# 0084_-_Power.net
KiCad netlist of a schematic drawn in Altium Designer
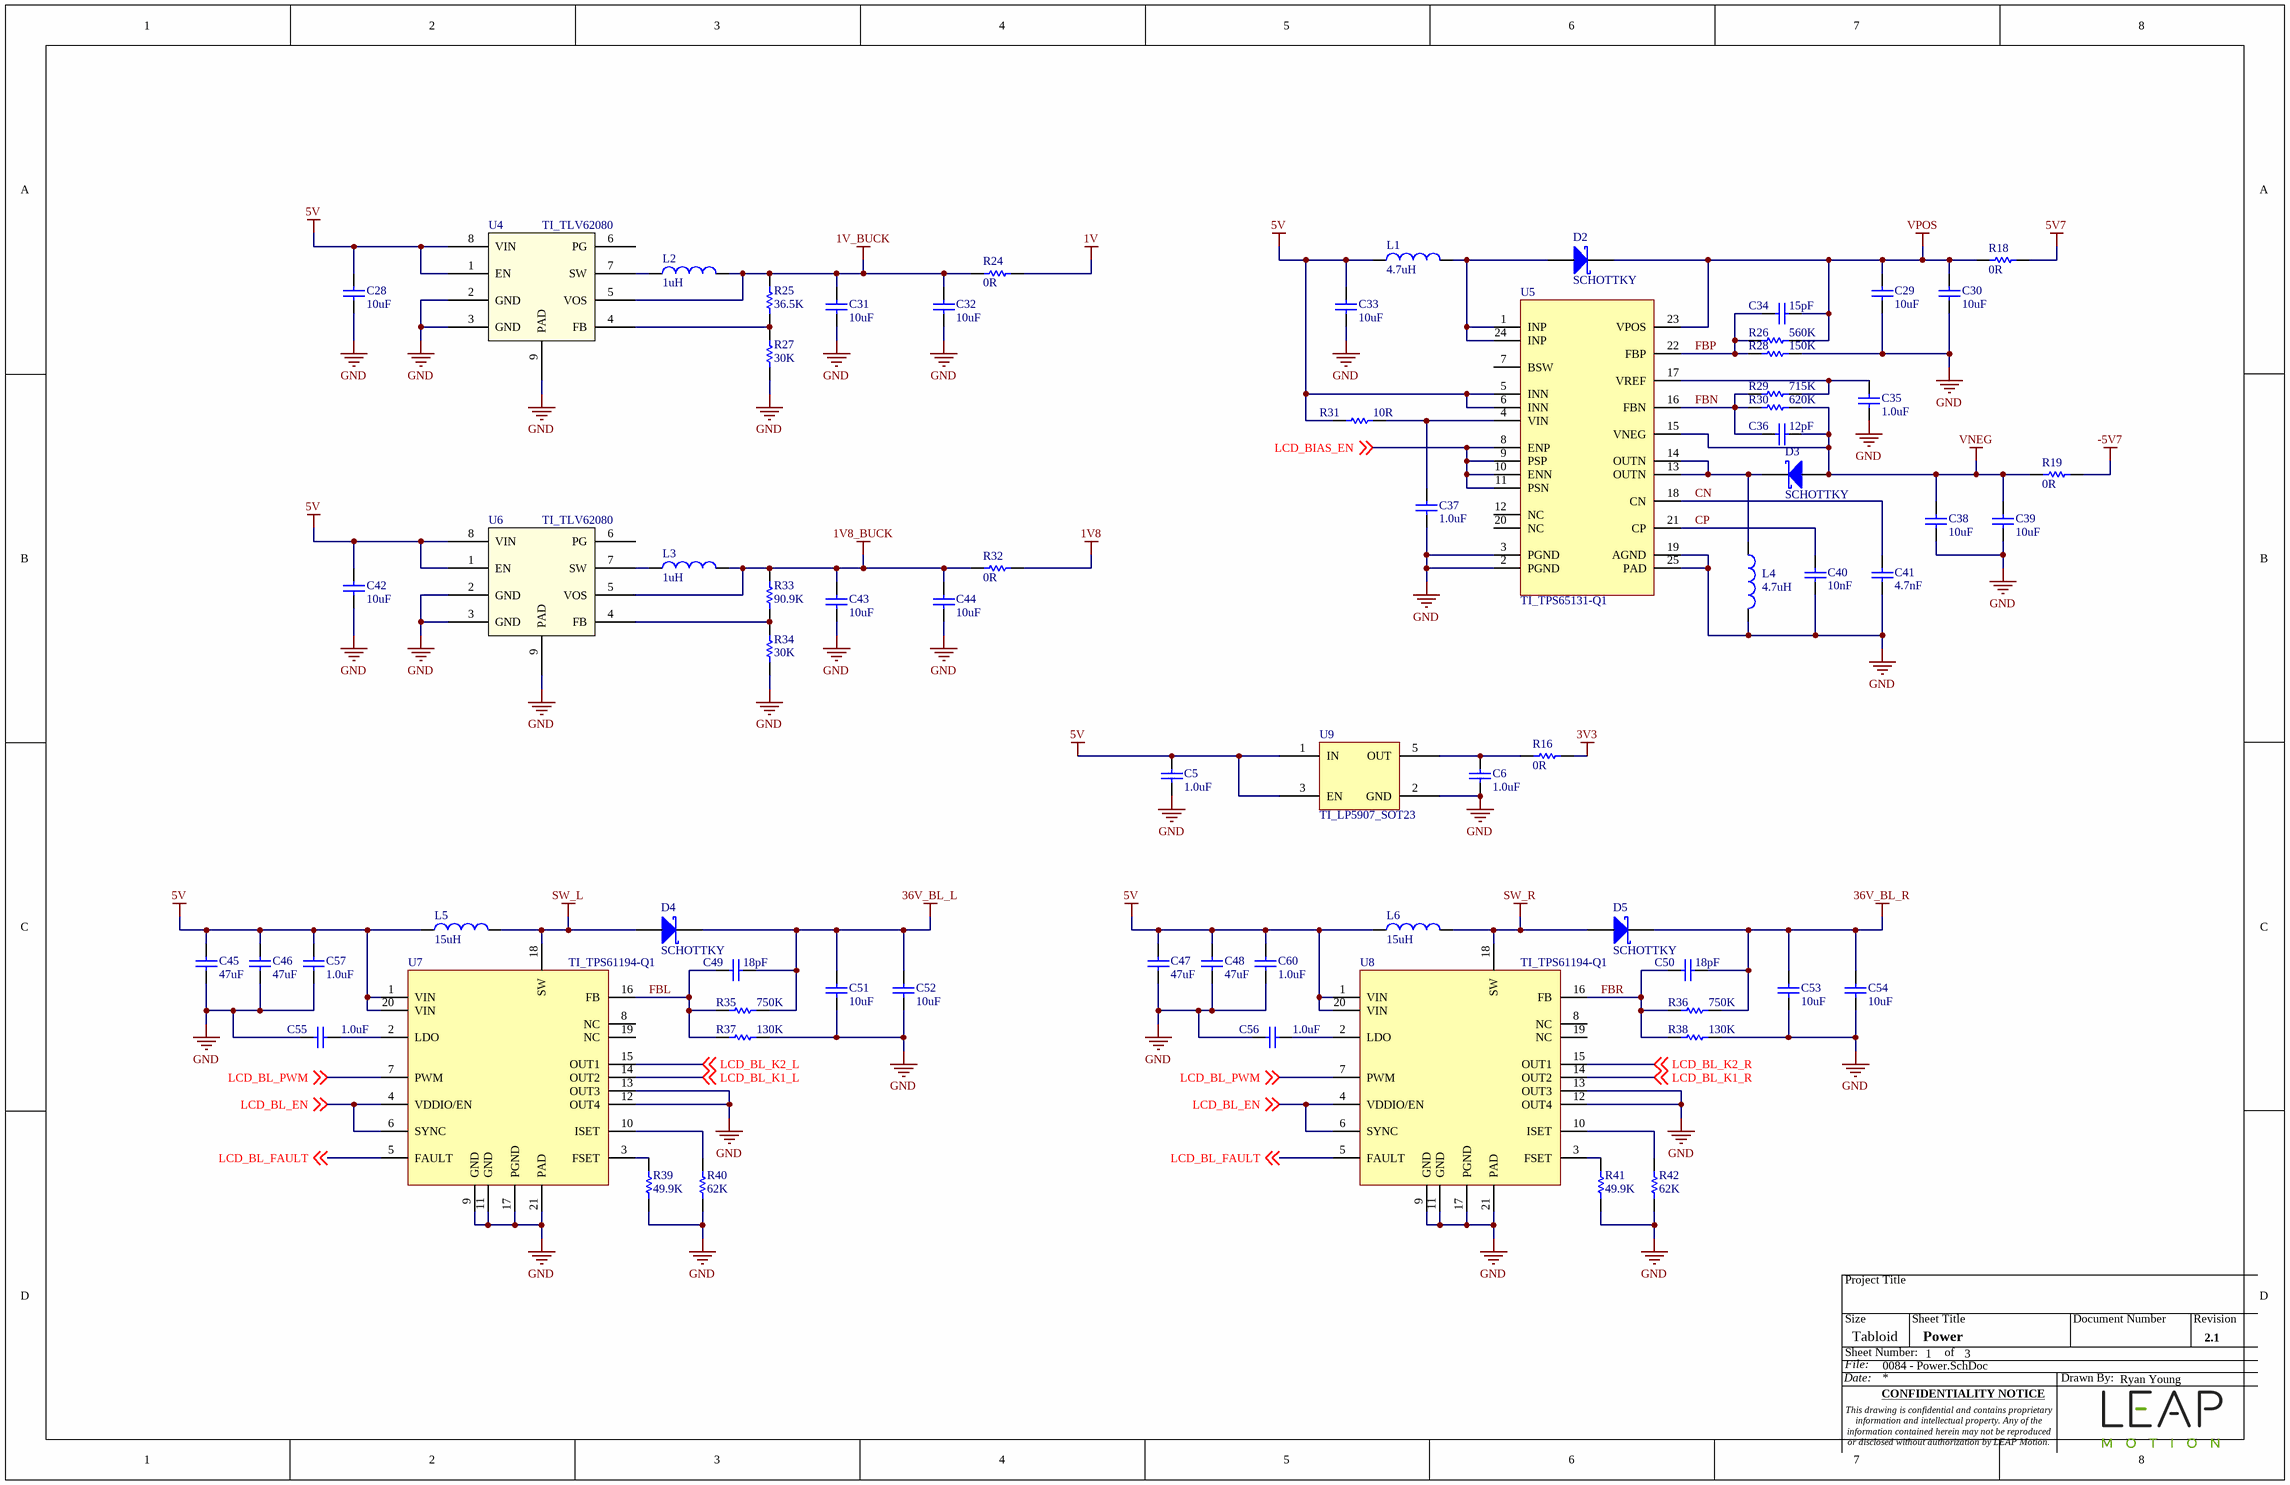
[diagram p0: 0084 - Power.SchDoc]

(export (version "E")
  (design (tool "Eeschema 10.0.6"))
  (components
    (comp (ref "C5")
      (value "1.0uF")
      (footprint "CAPC0402(1005)60_N")
      (description "Capacitor, 1.0uF, 10V, 10%, 0402, Ceramic, X5R")
      (fields
        (field (name "MANUFACTURER") "TDK")
        (field (name "TOLERANCE") "10%")
        (field (name "AUTHOR") "NR")
      )
      (libsource (lib "LEAPdb") (part "CAP"))
    )
    (comp (ref "C6")
      (value "1.0uF")
      (footprint "CAPC0402(1005)60_N")
      (description "Capacitor, 1.0uF, 10V, 10%, 0402, Ceramic, X5R")
      (fields
        (field (name "MANUFACTURER") "TDK")
        (field (name "TOLERANCE") "10%")
        (field (name "AUTHOR") "NR")
      )
      (libsource (lib "LEAPdb") (part "CAP"))
    )
    (comp (ref "C28")
      (value "10uF")
      (footprint "CAPC0603(1608)100_N")
      (description "Capacitor, 10uF, 10V, 10%, 0603, Ceramic, X5R")
      (fields
        (field (name "MANUFACTURER") "Murata")
        (field (name "TOLERANCE") "10%")
        (field (name "AUTHOR") "RY")
      )
      (libsource (lib "LEAPdb") (part "CAP"))
    )
    (comp (ref "C29")
      (value "10uF")
      (footprint "CAPC0603(1608)100_N")
      (description "Capacitor, 10uF, 10V, 10%, 0603, Ceramic, X5R")
      (fields
        (field (name "MANUFACTURER") "Murata")
        (field (name "TOLERANCE") "10%")
        (field (name "AUTHOR") "RY")
      )
      (libsource (lib "LEAPdb") (part "CAP"))
    )
    (comp (ref "C30")
      (value "10uF")
      (footprint "CAPC0603(1608)100_N")
      (description "Capacitor, 10uF, 10V, 10%, 0603, Ceramic, X5R")
      (fields
        (field (name "MANUFACTURER") "Murata")
        (field (name "TOLERANCE") "10%")
        (field (name "AUTHOR") "RY")
      )
      (libsource (lib "LEAPdb") (part "CAP"))
    )
    (comp (ref "C31")
      (value "10uF")
      (footprint "CAPC0603(1608)100_N")
      (description "Capacitor, 10uF, 10V, 10%, 0603, Ceramic, X5R")
      (fields
        (field (name "MANUFACTURER") "Murata")
        (field (name "TOLERANCE") "10%")
        (field (name "AUTHOR") "RY")
      )
      (libsource (lib "LEAPdb") (part "CAP"))
    )
    (comp (ref "C32")
      (value "10uF")
      (footprint "CAPC0603(1608)100_N")
      (description "Capacitor, 10uF, 10V, 10%, 0603, Ceramic, X5R")
      (fields
        (field (name "MANUFACTURER") "Murata")
        (field (name "TOLERANCE") "10%")
        (field (name "AUTHOR") "RY")
      )
      (libsource (lib "LEAPdb") (part "CAP"))
    )
    (comp (ref "C33")
      (value "10uF")
      (footprint "CAPC0603(1608)100_N")
      (description "Capacitor, 10uF, 10V, 10%, 0603, Ceramic, X5R")
      (fields
        (field (name "MANUFACTURER") "Murata")
        (field (name "TOLERANCE") "10%")
        (field (name "AUTHOR") "RY")
      )
      (libsource (lib "LEAPdb") (part "CAP"))
    )
    (comp (ref "C34")
      (value "15pF")
      (footprint "CAPC0201(0603)33_N")
      (description "Capacitor, 15pF, 50V, 2%, 0201, Ceramic, C0G(NP0)")
      (fields
        (field (name "MANUFACTURER") "Murata")
        (field (name "TOLERANCE") "2%")
        (field (name "AUTHOR") "RY")
      )
      (libsource (lib "LEAPdb") (part "CAP"))
    )
    (comp (ref "C35")
      (value "1.0uF")
      (footprint "CAPC0402(1005)60_N")
      (description "Capacitor, 1.0uF, 10V, 10%, 0402, Ceramic, X5R")
      (fields
        (field (name "MANUFACTURER") "TDK")
        (field (name "TOLERANCE") "10%")
        (field (name "AUTHOR") "NR")
      )
      (libsource (lib "LEAPdb") (part "CAP"))
    )
    (comp (ref "C36")
      (value "12pF")
      (footprint "CAPC0201(0603)33_N")
      (description "Capacitor, 12pF, 50V, 2%, 0201, Ceramic, C0G(NP0)")
      (fields
        (field (name "MANUFACTURER") "Murata")
        (field (name "TOLERANCE") "2%")
        (field (name "AUTHOR") "RY")
      )
      (libsource (lib "LEAPdb") (part "CAP"))
    )
    (comp (ref "C37")
      (value "1.0uF")
      (footprint "CAPC0402(1005)60_N")
      (description "Capacitor, 1.0uF, 10V, 10%, 0402, Ceramic, X5R")
      (fields
        (field (name "MANUFACTURER") "TDK")
        (field (name "TOLERANCE") "10%")
        (field (name "AUTHOR") "NR")
      )
      (libsource (lib "LEAPdb") (part "CAP"))
    )
    (comp (ref "C38")
      (value "10uF")
      (footprint "CAPC0603(1608)100_N")
      (description "Capacitor, 10uF, 10V, 10%, 0603, Ceramic, X5R")
      (fields
        (field (name "MANUFACTURER") "Murata")
        (field (name "TOLERANCE") "10%")
        (field (name "AUTHOR") "RY")
      )
      (libsource (lib "LEAPdb") (part "CAP"))
    )
    (comp (ref "C39")
      (value "10uF")
      (footprint "CAPC0603(1608)100_N")
      (description "Capacitor, 10uF, 10V, 10%, 0603, Ceramic, X5R")
      (fields
        (field (name "MANUFACTURER") "Murata")
        (field (name "TOLERANCE") "10%")
        (field (name "AUTHOR") "RY")
      )
      (libsource (lib "LEAPdb") (part "CAP"))
    )
    (comp (ref "C40")
      (value "10nF")
      (footprint "CAPC0402(1005)60_N")
      (description "Capacitor, 1.0uF, 10V, 10%, 0402, Ceramic, X5R")
      (fields
        (field (name "MANUFACTURER") "TDK")
        (field (name "TOLERANCE") "10%")
        (field (name "AUTHOR") "NR")
      )
      (libsource (lib "LEAPdb") (part "CAP"))
    )
    (comp (ref "C41")
      (value "4.7nF")
      (footprint "CAPC0402(1005)60_N")
      (description "Capacitor, 1.0uF, 10V, 10%, 0402, Ceramic, X5R")
      (fields
        (field (name "MANUFACTURER") "TDK")
        (field (name "TOLERANCE") "10%")
        (field (name "AUTHOR") "NR")
      )
      (libsource (lib "LEAPdb") (part "CAP"))
    )
    (comp (ref "C42")
      (value "10uF")
      (footprint "CAPC0603(1608)100_N")
      (description "Capacitor, 10uF, 10V, 10%, 0603, Ceramic, X5R")
      (fields
        (field (name "MANUFACTURER") "Murata")
        (field (name "TOLERANCE") "10%")
        (field (name "AUTHOR") "RY")
      )
      (libsource (lib "LEAPdb") (part "CAP"))
    )
    (comp (ref "C43")
      (value "10uF")
      (footprint "CAPC0603(1608)100_N")
      (description "Capacitor, 10uF, 10V, 10%, 0603, Ceramic, X5R")
      (fields
        (field (name "MANUFACTURER") "Murata")
        (field (name "TOLERANCE") "10%")
        (field (name "AUTHOR") "RY")
      )
      (libsource (lib "LEAPdb") (part "CAP"))
    )
    (comp (ref "C44")
      (value "10uF")
      (footprint "CAPC0603(1608)100_N")
      (description "Capacitor, 10uF, 10V, 10%, 0603, Ceramic, X5R")
      (fields
        (field (name "MANUFACTURER") "Murata")
        (field (name "TOLERANCE") "10%")
        (field (name "AUTHOR") "RY")
      )
      (libsource (lib "LEAPdb") (part "CAP"))
    )
    (comp (ref "C45")
      (value "47uF")
      (footprint "CAPC0805(2012)100_N")
      (description "Capacitor, 47uF, 10V, 20%, 0805, Ceramic, X5R")
      (fields
        (field (name "MANUFACTURER") "Murata")
        (field (name "TOLERANCE") "20%")
        (field (name "AUTHOR") "JDS")
      )
      (libsource (lib "LEAPdb") (part "CAP"))
    )
    (comp (ref "C46")
      (value "47uF")
      (footprint "CAPC0805(2012)100_N")
      (description "Capacitor, 47uF, 10V, 20%, 0805, Ceramic, X5R")
      (fields
        (field (name "MANUFACTURER") "Murata")
        (field (name "TOLERANCE") "20%")
        (field (name "AUTHOR") "JDS")
      )
      (libsource (lib "LEAPdb") (part "CAP"))
    )
    (comp (ref "C47")
      (value "47uF")
      (footprint "CAPC0805(2012)100_N")
      (description "Capacitor, 47uF, 10V, 20%, 0805, Ceramic, X5R")
      (fields
        (field (name "MANUFACTURER") "Murata")
        (field (name "TOLERANCE") "20%")
        (field (name "AUTHOR") "JDS")
      )
      (libsource (lib "LEAPdb") (part "CAP"))
    )
    (comp (ref "C48")
      (value "47uF")
      (footprint "CAPC0805(2012)100_N")
      (description "Capacitor, 47uF, 10V, 20%, 0805, Ceramic, X5R")
      (fields
        (field (name "MANUFACTURER") "Murata")
        (field (name "TOLERANCE") "20%")
        (field (name "AUTHOR") "JDS")
      )
      (libsource (lib "LEAPdb") (part "CAP"))
    )
    (comp (ref "C49")
      (value "18pF")
      (footprint "CAPC0201(0603)33_N")
      (description "Capacitor, 18pF, 50V, 2%, 0201, Ceramic, C0G(NP0)")
      (fields
        (field (name "MANUFACTURER") "Murata")
        (field (name "TOLERANCE") "2%")
        (field (name "AUTHOR") "RY")
      )
      (libsource (lib "LEAPdb") (part "CAP"))
    )
    (comp (ref "C50")
      (value "18pF")
      (footprint "CAPC0201(0603)33_N")
      (description "Capacitor, 18pF, 50V, 2%, 0201, Ceramic, C0G(NP0)")
      (fields
        (field (name "MANUFACTURER") "Murata")
        (field (name "TOLERANCE") "2%")
        (field (name "AUTHOR") "RY")
      )
      (libsource (lib "LEAPdb") (part "CAP"))
    )
    (comp (ref "C51")
      (value "10uF")
      (footprint "CAPC1206(3216)170_N")
      (description "Capacitor, 10uF, 50V, 10%, 1206, Ceramic, X7R")
      (fields
        (field (name "MANUFACTURER") "Samsung")
        (field (name "TOLERANCE") "10%")
        (field (name "AUTHOR") "RY")
      )
      (libsource (lib "LEAPdb") (part "CAP"))
    )
    (comp (ref "C52")
      (value "10uF")
      (footprint "CAPC1206(3216)170_N")
      (description "Capacitor, 10uF, 50V, 10%, 1206, Ceramic, X7R")
      (fields
        (field (name "MANUFACTURER") "Samsung")
        (field (name "TOLERANCE") "10%")
        (field (name "AUTHOR") "RY")
      )
      (libsource (lib "LEAPdb") (part "CAP"))
    )
    (comp (ref "C53")
      (value "10uF")
      (footprint "CAPC1206(3216)170_N")
      (description "Capacitor, 10uF, 50V, 10%, 1206, Ceramic, X7R")
      (fields
        (field (name "MANUFACTURER") "Samsung")
        (field (name "TOLERANCE") "10%")
        (field (name "AUTHOR") "RY")
      )
      (libsource (lib "LEAPdb") (part "CAP"))
    )
    (comp (ref "C54")
      (value "10uF")
      (footprint "CAPC1206(3216)170_N")
      (description "Capacitor, 10uF, 50V, 10%, 1206, Ceramic, X7R")
      (fields
        (field (name "MANUFACTURER") "Samsung")
        (field (name "TOLERANCE") "10%")
        (field (name "AUTHOR") "RY")
      )
      (libsource (lib "LEAPdb") (part "CAP"))
    )
    (comp (ref "C55")
      (value "1.0uF")
      (footprint "CAPC0402(1005)60_N")
      (description "Capacitor, 1.0uF, 10V, 10%, 0402, Ceramic, X5R")
      (fields
        (field (name "MANUFACTURER") "TDK")
        (field (name "TOLERANCE") "10%")
        (field (name "AUTHOR") "NR")
      )
      (libsource (lib "LEAPdb") (part "CAP"))
    )
    (comp (ref "C56")
      (value "1.0uF")
      (footprint "CAPC0402(1005)60_N")
      (description "Capacitor, 1.0uF, 10V, 10%, 0402, Ceramic, X5R")
      (fields
        (field (name "MANUFACTURER") "TDK")
        (field (name "TOLERANCE") "10%")
        (field (name "AUTHOR") "NR")
      )
      (libsource (lib "LEAPdb") (part "CAP"))
    )
    (comp (ref "C57")
      (value "1.0uF")
      (footprint "CAPC0402(1005)60_N")
      (description "Capacitor, 1.0uF, 10V, 10%, 0402, Ceramic, X5R")
      (fields
        (field (name "MANUFACTURER") "TDK")
        (field (name "TOLERANCE") "10%")
        (field (name "AUTHOR") "NR")
      )
      (libsource (lib "LEAPdb") (part "CAP"))
    )
    (comp (ref "C60")
      (value "1.0uF")
      (footprint "CAPC0402(1005)60_N")
      (description "Capacitor, 1.0uF, 10V, 10%, 0402, Ceramic, X5R")
      (fields
        (field (name "MANUFACTURER") "TDK")
        (field (name "TOLERANCE") "10%")
        (field (name "AUTHOR") "NR")
      )
      (libsource (lib "LEAPdb") (part "CAP"))
    )
    (comp (ref "D2")
      (value "SCHOTTKY")
      (footprint "Toshiba_CUS10S40,H3F")
      (description "Diode, -40C - 150C, SOD-323")
      (fields (field (name "MANUFACTURER") "Toshiba"))
      (libsource (lib "LEAPdb") (part "SCHOTTKY"))
    )
    (comp (ref "D3")
      (value "SCHOTTKY")
      (footprint "Toshiba_CUS10S40,H3F")
      (description "Diode, -40C - 150C, SOD-323")
      (fields (field (name "MANUFACTURER") "Toshiba"))
      (libsource (lib "LEAPdb") (part "SCHOTTKY"))
    )
    (comp (ref "D4")
      (value "SCHOTTKY")
      (footprint "Toshiba_CUS10S40,H3F")
      (description "Diode, -40C - 150C, SOD-323")
      (fields (field (name "MANUFACTURER") "Toshiba"))
      (libsource (lib "LEAPdb") (part "SCHOTTKY"))
    )
    (comp (ref "D5")
      (value "SCHOTTKY")
      (footprint "Toshiba_CUS10S40,H3F")
      (description "Diode, -40C - 150C, SOD-323")
      (fields (field (name "MANUFACTURER") "Toshiba"))
      (libsource (lib "LEAPdb") (part "SCHOTTKY"))
    )
    (comp (ref "L1")
      (value "4.7uH")
      (footprint "INDC2520X10N")
      (description "FIXED IND 4.7UH 1.4A 216 MOHM")
      (fields
        (field (name "MANUFACTURER") "Murata")
        (field (name "TOLERANCE") "20%")
        (field (name "AUTHOR") "RY")
      )
      (libsource (lib "LEAPdb") (part "Inductor"))
    )
    (comp (ref "L2")
      (value "1uH")
      (footprint "INDC2520X10N")
      (description "INDUCTOR 1.0UH 20% 1600MA 1008")
      (fields
        (field (name "MANUFACTURER") "Murata")
        (field (name "TOLERANCE") "20%")
        (field (name "AUTHOR") "NR")
      )
      (libsource (lib "LEAPdb") (part "Inductor"))
    )
    (comp (ref "L3")
      (value "1uH")
      (footprint "INDC2520X10N")
      (description "INDUCTOR 1.0UH 20% 1600MA 1008")
      (fields
        (field (name "MANUFACTURER") "Murata")
        (field (name "TOLERANCE") "20%")
        (field (name "AUTHOR") "NR")
      )
      (libsource (lib "LEAPdb") (part "Inductor"))
    )
    (comp (ref "L4")
      (value "4.7uH")
      (footprint "INDC2520X10N")
      (description "FIXED IND 4.7UH 1.4A 216 MOHM")
      (fields
        (field (name "MANUFACTURER") "Murata")
        (field (name "TOLERANCE") "20%")
        (field (name "AUTHOR") "RY")
      )
      (libsource (lib "LEAPdb") (part "Inductor"))
    )
    (comp (ref "L5")
      (value "15uH")
      (footprint "Coilcraft_XAL4040-153MEB")
      (description "Fixed Inductors XAL4040 AEC-Q200 15 uH 20 % 2.8 A")
      (fields
        (field (name "MANUFACTURER") "Coilcraft")
        (field (name "TOLERANCE") "20%")
        (field (name "AUTHOR") "RY")
      )
      (libsource (lib "LEAPdb") (part "Inductor"))
    )
    (comp (ref "L6")
      (value "15uH")
      (footprint "Coilcraft_XAL4040-153MEB")
      (description "Fixed Inductors XAL4040 AEC-Q200 15 uH 20 % 2.8 A")
      (fields
        (field (name "MANUFACTURER") "Coilcraft")
        (field (name "TOLERANCE") "20%")
        (field (name "AUTHOR") "RY")
      )
      (libsource (lib "LEAPdb") (part "Inductor"))
    )
    (comp (ref "R16")
      (value "0R")
      (footprint "RESC0402(1005)_N")
      (description "Resistor, 0R, 1/10W, Jumper, 0402")
      (fields
        (field (name "MANUFACTURER") "Panasonic Electronic Components")
        (field (name "TOLERANCE") "Jumper")
        (field (name "AUTHOR") "NR")
      )
      (libsource (lib "LEAPdb") (part "RES"))
    )
    (comp (ref "R18")
      (value "0R")
      (footprint "RESC0402(1005)_N")
      (description "Resistor, 0R, 1/10W, Jumper, 0402")
      (fields
        (field (name "MANUFACTURER") "Panasonic Electronic Components")
        (field (name "TOLERANCE") "Jumper")
        (field (name "AUTHOR") "NR")
      )
      (libsource (lib "LEAPdb") (part "RES"))
    )
    (comp (ref "R19")
      (value "0R")
      (footprint "RESC0402(1005)_N")
      (description "Resistor, 0R, 1/10W, Jumper, 0402")
      (fields
        (field (name "MANUFACTURER") "Panasonic Electronic Components")
        (field (name "TOLERANCE") "Jumper")
        (field (name "AUTHOR") "NR")
      )
      (libsource (lib "LEAPdb") (part "RES"))
    )
    (comp (ref "R24")
      (value "0R")
      (footprint "RESC0402(1005)_N")
      (description "Resistor, 0R, 1/10W, Jumper, 0402")
      (fields
        (field (name "MANUFACTURER") "Panasonic Electronic Components")
        (field (name "TOLERANCE") "Jumper")
        (field (name "AUTHOR") "NR")
      )
      (libsource (lib "LEAPdb") (part "RES"))
    )
    (comp (ref "R25")
      (value "36.5K")
      (footprint "RESC0201(0603)_N")
      (description "Resistor, 36.5K, 1/20W, 1%, 0201")
      (fields
        (field (name "MANUFACTURER") "Panasonic Electronic Components")
        (field (name "TOLERANCE") "1%")
        (field (name "AUTHOR") "RY")
      )
      (libsource (lib "LEAPdb") (part "RES"))
    )
    (comp (ref "R26")
      (value "560K")
      (footprint "RESC0201(0603)_N")
      (description "Resistor, 560K, 1/20W, 1%, 0201")
      (fields
        (field (name "MANUFACTURER") "Yageo")
        (field (name "TOLERANCE") "1%")
        (field (name "AUTHOR") "Ry")
      )
      (libsource (lib "LEAPdb") (part "RES"))
    )
    (comp (ref "R27")
      (value "30K")
      (footprint "RESC0201(0603)_N")
      (description "Resistor, 30K, 1/20W, 1%, 0201")
      (fields
        (field (name "MANUFACTURER") "Panasonic Electronic Components")
        (field (name "TOLERANCE") "1%")
        (field (name "AUTHOR") "RY")
      )
      (libsource (lib "LEAPdb") (part "RES"))
    )
    (comp (ref "R28")
      (value "150K")
      (footprint "RESC0201(0603)_N")
      (description "Resistor, 150K, 1/20W, 1%, 0201")
      (fields
        (field (name "MANUFACTURER") "Panasonic Electronic Components")
        (field (name "TOLERANCE") "1%")
        (field (name "AUTHOR") "RY")
      )
      (libsource (lib "LEAPdb") (part "RES"))
    )
    (comp (ref "R29")
      (value "715K")
      (footprint "RESC0201(0603)_N")
      (description "Resistor, 715K, 1/20W, 1%, 0201")
      (fields
        (field (name "MANUFACTURER") "Yageo")
        (field (name "TOLERANCE") "1%")
        (field (name "AUTHOR") "RY")
      )
      (libsource (lib "LEAPdb") (part "RES"))
    )
    (comp (ref "R30")
      (value "620K")
      (footprint "RESC0201(0603)_N")
      (description "Resistor, 620K, 1/20W, 1%, 0201")
      (fields
        (field (name "MANUFACTURER") "Panasonic Electronic Components")
        (field (name "TOLERANCE") "1%")
        (field (name "AUTHOR") "RY")
      )
      (libsource (lib "LEAPdb") (part "RES"))
    )
    (comp (ref "R31")
      (value "10R")
      (footprint "RESC0402(1005)_N")
      (description "Resistor, 10R, 1/10W, 1%, 0402")
      (fields
        (field (name "MANUFACTURER") "Panasonic")
        (field (name "TOLERANCE") "1%")
        (field (name "AUTHOR") "JDS")
      )
      (libsource (lib "LEAPdb") (part "RES"))
    )
    (comp (ref "R32")
      (value "0R")
      (footprint "RESC0402(1005)_N")
      (description "Resistor, 0R, 1/10W, Jumper, 0402")
      (fields
        (field (name "MANUFACTURER") "Panasonic Electronic Components")
        (field (name "TOLERANCE") "Jumper")
        (field (name "AUTHOR") "NR")
      )
      (libsource (lib "LEAPdb") (part "RES"))
    )
    (comp (ref "R33")
      (value "90.9K")
      (footprint "RESC0201(0603)_N")
      (description "Resistor, 90.9K, 1/20W, 1%, 0201")
      (fields
        (field (name "MANUFACTURER") "Panasonic Electronic Components")
        (field (name "TOLERANCE") "1%")
        (field (name "AUTHOR") "RY")
      )
      (libsource (lib "LEAPdb") (part "RES"))
    )
    (comp (ref "R34")
      (value "30K")
      (footprint "RESC0201(0603)_N")
      (description "Resistor, 30K, 1/20W, 1%, 0201")
      (fields
        (field (name "MANUFACTURER") "Panasonic Electronic Components")
        (field (name "TOLERANCE") "1%")
        (field (name "AUTHOR") "RY")
      )
      (libsource (lib "LEAPdb") (part "RES"))
    )
    (comp (ref "R35")
      (value "750K")
      (footprint "RESC0201(0603)_N")
      (description "Resistor, 750K, 1/20W, 1%, 0201")
      (fields
        (field (name "MANUFACTURER") "Panasonic Electronic Components")
        (field (name "TOLERANCE") "1%")
        (field (name "AUTHOR") "RY")
      )
      (libsource (lib "LEAPdb") (part "RES"))
    )
    (comp (ref "R36")
      (value "750K")
      (footprint "RESC0201(0603)_N")
      (description "Resistor, 750K, 1/20W, 1%, 0201")
      (fields
        (field (name "MANUFACTURER") "Panasonic Electronic Components")
        (field (name "TOLERANCE") "1%")
        (field (name "AUTHOR") "RY")
      )
      (libsource (lib "LEAPdb") (part "RES"))
    )
    (comp (ref "R37")
      (value "130K")
      (footprint "RESC0201(0603)_N")
      (description "Resistor, 130K, 1/20W, 1%, 0201")
      (fields
        (field (name "MANUFACTURER") "Panasonic Electronic Components")
        (field (name "TOLERANCE") "1%")
        (field (name "AUTHOR") "RY")
      )
      (libsource (lib "LEAPdb") (part "RES"))
    )
    (comp (ref "R38")
      (value "130K")
      (footprint "RESC0201(0603)_N")
      (description "Resistor, 130K, 1/20W, 1%, 0201")
      (fields
        (field (name "MANUFACTURER") "Panasonic Electronic Components")
        (field (name "TOLERANCE") "1%")
        (field (name "AUTHOR") "RY")
      )
      (libsource (lib "LEAPdb") (part "RES"))
    )
    (comp (ref "R39")
      (value "49.9K")
      (footprint "RESC0201(0603)_N")
      (description "Resistor, 49.9K, 1/20W, 1%, 0201")
      (fields
        (field (name "MANUFACTURER") "Panasonic Electronic Components")
        (field (name "TOLERANCE") "1%")
        (field (name "AUTHOR") "JDS")
      )
      (libsource (lib "LEAPdb") (part "RES"))
    )
    (comp (ref "R40")
      (value "62K")
      (footprint "RESC0201(0603)_N")
      (description "Resistor, 62K, 1/20W, 1%, 0201")
      (fields
        (field (name "MANUFACTURER") "Panasonic Electronic Components")
        (field (name "TOLERANCE") "1%")
        (field (name "AUTHOR") "NR")
      )
      (libsource (lib "LEAPdb") (part "RES"))
    )
    (comp (ref "R41")
      (value "49.9K")
      (footprint "RESC0201(0603)_N")
      (description "Resistor, 49.9K, 1/20W, 1%, 0201")
      (fields
        (field (name "MANUFACTURER") "Panasonic Electronic Components")
        (field (name "TOLERANCE") "1%")
        (field (name "AUTHOR") "JDS")
      )
      (libsource (lib "LEAPdb") (part "RES"))
    )
    (comp (ref "R42")
      (value "62K")
      (footprint "RESC0201(0603)_N")
      (description "Resistor, 62K, 1/20W, 1%, 0201")
      (fields
        (field (name "MANUFACTURER") "Panasonic Electronic Components")
        (field (name "TOLERANCE") "1%")
        (field (name "AUTHOR") "NR")
      )
      (libsource (lib "LEAPdb") (part "RES"))
    )
    (comp (ref "U4")
      (value "TI_TLV62080")
      (footprint "TI_TLV62080")
      (description "IC REG BUCK ADJ 1.2A SYNC 8WSON")
      (fields (field (name "MANUFACTURER") "TI") (field (name "AUTHOR") "RY"))
      (libsource (lib "LEAPdb") (part "TI_TLV62080"))
    )
    (comp (ref "U5")
      (value "TI_TPS65131-Q1")
      (footprint "TI_TPS65131-Q1")
      (description "IC REG BCK BST INV ADJ DL 24VQFN")
      (fields (field (name "MANUFACTURER") "TI") (field (name "AUTHOR") "RY"))
      (libsource (lib "LEAPdb") (part "TI_TPS65131-Q1"))
    )
    (comp (ref "U6")
      (value "TI_TLV62080")
      (footprint "TI_TLV62080")
      (description "IC REG BUCK ADJ 1.2A SYNC 8WSON")
      (fields (field (name "MANUFACTURER") "TI") (field (name "AUTHOR") "RY"))
      (libsource (lib "LEAPdb") (part "TI_TLV62080"))
    )
    (comp (ref "U7")
      (value "TI_TPS61194-Q1")
      (footprint "TI_TPS61194-Q1")
      (description "IC LED DRIVER 20TSSOP")
      (fields (field (name "MANUFACTURER") "TI") (field (name "AUTHOR") "RY"))
      (libsource (lib "LEAPdb") (part "TI_TPS61194-Q1"))
    )
    (comp (ref "U8")
      (value "TI_TPS61194-Q1")
      (footprint "TI_TPS61194-Q1")
      (description "IC LED DRIVER 20TSSOP")
      (fields (field (name "MANUFACTURER") "TI") (field (name "AUTHOR") "RY"))
      (libsource (lib "LEAPdb") (part "TI_TPS61194-Q1"))
    )
    (comp (ref "U9")
      (value "TI_LP5907_SOT23")
      (footprint "TI_LP5907_SOT23")
      (description "3.3 V LDO Voltage Regulators 250mA Ultra-Lo Noise LDO Reg")
      (fields (field (name "MANUFACTURER") "TI") (field (name "AUTHOR") "JDS"))
      (libsource (lib "LEAPdb") (part "TI_LP5907_SOT23"))
    )
  )
  (nets
    (net (code "1") (name "-5V7") (class "Default")
      (node (ref "R19") (pin "2") (pinfunction "2_2") (pintype "passive"))
    )
    (net (code "2") (name "/CN") (class "Default")
      (node (ref "C41") (pin "1") (pinfunction "1_1") (pintype "passive"))
      (node (ref "U5") (pin "18") (pinfunction "CN_18") (pintype "passive"))
    )
    (net (code "3") (name "/CP") (class "Default")
      (node (ref "C40") (pin "1") (pinfunction "1_1") (pintype "passive"))
      (node (ref "U5") (pin "21") (pinfunction "CP_21") (pintype "passive"))
    )
    (net (code "4") (name "/FBL") (class "Default")
      (node (ref "C49") (pin "2") (pinfunction "2_2") (pintype "passive"))
      (node (ref "R35") (pin "2") (pinfunction "2_2") (pintype "passive"))
      (node (ref "R37") (pin "2") (pinfunction "2_2") (pintype "passive"))
      (node (ref "U7") (pin "16") (pinfunction "FB_16") (pintype "passive"))
    )
    (net (code "5") (name "/FBN") (class "Default")
      (node (ref "C36") (pin "2") (pinfunction "2_2") (pintype "passive"))
      (node (ref "R29") (pin "2") (pinfunction "2_2") (pintype "passive"))
      (node (ref "R30") (pin "2") (pinfunction "2_2") (pintype "passive"))
      (node (ref "U5") (pin "16") (pinfunction "FBN_16") (pintype "passive"))
    )
    (net (code "6") (name "/FBP") (class "Default")
      (node (ref "C34") (pin "2") (pinfunction "2_2") (pintype "passive"))
      (node (ref "R26") (pin "2") (pinfunction "2_2") (pintype "passive"))
      (node (ref "R28") (pin "2") (pinfunction "2_2") (pintype "passive"))
      (node (ref "U5") (pin "22") (pinfunction "FBP_22") (pintype "passive"))
    )
    (net (code "7") (name "/FBR") (class "Default")
      (node (ref "C50") (pin "2") (pinfunction "2_2") (pintype "passive"))
      (node (ref "R36") (pin "2") (pinfunction "2_2") (pintype "passive"))
      (node (ref "R38") (pin "2") (pinfunction "2_2") (pintype "passive"))
      (node (ref "U8") (pin "16") (pinfunction "FB_16") (pintype "passive"))
    )
    (net (code "8") (name "1V") (class "Default")
      (node (ref "R24") (pin "2") (pinfunction "2_2") (pintype "passive"))
    )
    (net (code "9") (name "1V8") (class "Default")
      (node (ref "R32") (pin "2") (pinfunction "2_2") (pintype "passive"))
    )
    (net (code "10") (name "1V8_BUCK") (class "Default")
      (node (ref "C43") (pin "2") (pinfunction "2_2") (pintype "passive"))
      (node (ref "C44") (pin "2") (pinfunction "2_2") (pintype "passive"))
      (node (ref "L3") (pin "2") (pinfunction "2_2") (pintype "passive"))
      (node (ref "R32") (pin "1") (pinfunction "1_1") (pintype "passive"))
      (node (ref "R33") (pin "2") (pinfunction "2_2") (pintype "passive"))
      (node (ref "U6") (pin "5") (pinfunction "VOS_5") (pintype "passive"))
    )
    (net (code "11") (name "1V_BUCK") (class "Default")
      (node (ref "C31") (pin "2") (pinfunction "2_2") (pintype "passive"))
      (node (ref "C32") (pin "2") (pinfunction "2_2") (pintype "passive"))
      (node (ref "L2") (pin "2") (pinfunction "2_2") (pintype "passive"))
      (node (ref "R24") (pin "1") (pinfunction "1_1") (pintype "passive"))
      (node (ref "R25") (pin "2") (pinfunction "2_2") (pintype "passive"))
      (node (ref "U4") (pin "5") (pinfunction "VOS_5") (pintype "passive"))
    )
    (net (code "12") (name "3V3") (class "Default")
      (node (ref "R16") (pin "2") (pinfunction "2_2") (pintype "passive"))
    )
    (net (code "13") (name "5V") (class "Default")
      (node (ref "C28") (pin "2") (pinfunction "2_2") (pintype "passive"))
      (node (ref "C33") (pin "2") (pinfunction "2_2") (pintype "passive"))
      (node (ref "C42") (pin "2") (pinfunction "2_2") (pintype "passive"))
      (node (ref "C45") (pin "2") (pinfunction "2_2") (pintype "passive"))
      (node (ref "C46") (pin "2") (pinfunction "2_2") (pintype "passive"))
      (node (ref "C47") (pin "2") (pinfunction "2_2") (pintype "passive"))
      (node (ref "C48") (pin "2") (pinfunction "2_2") (pintype "passive"))
      (node (ref "C5") (pin "1") (pinfunction "1_1") (pintype "passive"))
      (node (ref "C57") (pin "2") (pinfunction "2_2") (pintype "passive"))
      (node (ref "C60") (pin "2") (pinfunction "2_2") (pintype "passive"))
      (node (ref "L1") (pin "1") (pinfunction "1_1") (pintype "passive"))
      (node (ref "L5") (pin "1") (pinfunction "1_1") (pintype "passive"))
      (node (ref "L6") (pin "1") (pinfunction "1_1") (pintype "passive"))
      (node (ref "R31") (pin "1") (pinfunction "1_1") (pintype "passive"))
      (node (ref "U4") (pin "1") (pinfunction "EN_1") (pintype "passive"))
      (node (ref "U4") (pin "8") (pinfunction "VIN_8") (pintype "passive"))
      (node (ref "U5") (pin "5") (pinfunction "INN_5") (pintype "passive"))
      (node (ref "U5") (pin "6") (pinfunction "INN_6") (pintype "passive"))
      (node (ref "U6") (pin "1") (pinfunction "EN_1") (pintype "passive"))
      (node (ref "U6") (pin "8") (pinfunction "VIN_8") (pintype "passive"))
      (node (ref "U7") (pin "1") (pinfunction "VIN_1") (pintype "passive"))
      (node (ref "U7") (pin "20") (pinfunction "VIN_20") (pintype "passive"))
      (node (ref "U8") (pin "1") (pinfunction "VIN_1") (pintype "passive"))
      (node (ref "U8") (pin "20") (pinfunction "VIN_20") (pintype "passive"))
      (node (ref "U9") (pin "1") (pinfunction "IN_1") (pintype "passive"))
      (node (ref "U9") (pin "3") (pinfunction "EN_3") (pintype "passive"))
    )
    (net (code "14") (name "5V7") (class "Default")
      (node (ref "R18") (pin "2") (pinfunction "2_2") (pintype "passive"))
    )
    (net (code "15") (name "36V_BL_L") (class "Default")
      (node (ref "C49") (pin "1") (pinfunction "1_1") (pintype "passive"))
      (node (ref "C51") (pin "2") (pinfunction "2_2") (pintype "passive"))
      (node (ref "C52") (pin "2") (pinfunction "2_2") (pintype "passive"))
      (node (ref "D4") (pin "K") (pinfunction "K_K") (pintype "passive"))
      (node (ref "R35") (pin "1") (pinfunction "1_1") (pintype "passive"))
    )
    (net (code "16") (name "36V_BL_R") (class "Default")
      (node (ref "C50") (pin "1") (pinfunction "1_1") (pintype "passive"))
      (node (ref "C53") (pin "2") (pinfunction "2_2") (pintype "passive"))
      (node (ref "C54") (pin "2") (pinfunction "2_2") (pintype "passive"))
      (node (ref "D5") (pin "K") (pinfunction "K_K") (pintype "passive"))
      (node (ref "R36") (pin "1") (pinfunction "1_1") (pintype "passive"))
    )
    (net (code "17") (name "GND") (class "Default")
      (node (ref "C28") (pin "1") (pinfunction "1_1") (pintype "passive"))
      (node (ref "C29") (pin "1") (pinfunction "1_1") (pintype "passive"))
      (node (ref "C30") (pin "1") (pinfunction "1_1") (pintype "passive"))
      (node (ref "C31") (pin "1") (pinfunction "1_1") (pintype "passive"))
      (node (ref "C32") (pin "1") (pinfunction "1_1") (pintype "passive"))
      (node (ref "C33") (pin "1") (pinfunction "1_1") (pintype "passive"))
      (node (ref "C35") (pin "2") (pinfunction "2_2") (pintype "passive"))
      (node (ref "C37") (pin "1") (pinfunction "1_1") (pintype "passive"))
      (node (ref "C38") (pin "1") (pinfunction "1_1") (pintype "passive"))
      (node (ref "C39") (pin "1") (pinfunction "1_1") (pintype "passive"))
      (node (ref "C40") (pin "2") (pinfunction "2_2") (pintype "passive"))
      (node (ref "C41") (pin "2") (pinfunction "2_2") (pintype "passive"))
      (node (ref "C42") (pin "1") (pinfunction "1_1") (pintype "passive"))
      (node (ref "C43") (pin "1") (pinfunction "1_1") (pintype "passive"))
      (node (ref "C44") (pin "1") (pinfunction "1_1") (pintype "passive"))
      (node (ref "C45") (pin "1") (pinfunction "1_1") (pintype "passive"))
      (node (ref "C46") (pin "1") (pinfunction "1_1") (pintype "passive"))
      (node (ref "C47") (pin "1") (pinfunction "1_1") (pintype "passive"))
      (node (ref "C48") (pin "1") (pinfunction "1_1") (pintype "passive"))
      (node (ref "C5") (pin "2") (pinfunction "2_2") (pintype "passive"))
      (node (ref "C51") (pin "1") (pinfunction "1_1") (pintype "passive"))
      (node (ref "C52") (pin "1") (pinfunction "1_1") (pintype "passive"))
      (node (ref "C53") (pin "1") (pinfunction "1_1") (pintype "passive"))
      (node (ref "C54") (pin "1") (pinfunction "1_1") (pintype "passive"))
      (node (ref "C55") (pin "2") (pinfunction "2_2") (pintype "passive"))
      (node (ref "C56") (pin "2") (pinfunction "2_2") (pintype "passive"))
      (node (ref "C57") (pin "1") (pinfunction "1_1") (pintype "passive"))
      (node (ref "C6") (pin "2") (pinfunction "2_2") (pintype "passive"))
      (node (ref "C60") (pin "1") (pinfunction "1_1") (pintype "passive"))
      (node (ref "L4") (pin "2") (pinfunction "2_2") (pintype "passive"))
      (node (ref "R27") (pin "1") (pinfunction "1_1") (pintype "passive"))
      (node (ref "R28") (pin "1") (pinfunction "1_1") (pintype "passive"))
      (node (ref "R34") (pin "1") (pinfunction "1_1") (pintype "passive"))
      (node (ref "R37") (pin "1") (pinfunction "1_1") (pintype "passive"))
      (node (ref "R38") (pin "1") (pinfunction "1_1") (pintype "passive"))
      (node (ref "R39") (pin "1") (pinfunction "1_1") (pintype "passive"))
      (node (ref "R40") (pin "1") (pinfunction "1_1") (pintype "passive"))
      (node (ref "R41") (pin "1") (pinfunction "1_1") (pintype "passive"))
      (node (ref "R42") (pin "1") (pinfunction "1_1") (pintype "passive"))
      (node (ref "U4") (pin "2") (pinfunction "GND_2") (pintype "passive"))
      (node (ref "U4") (pin "3") (pinfunction "GND_3") (pintype "passive"))
      (node (ref "U4") (pin "9") (pinfunction "PAD_9") (pintype "passive"))
      (node (ref "U5") (pin "19") (pinfunction "AGND_19") (pintype "passive"))
      (node (ref "U5") (pin "2") (pinfunction "PGND_2") (pintype "passive"))
      (node (ref "U5") (pin "25") (pinfunction "PAD_25") (pintype "passive"))
      (node (ref "U5") (pin "3") (pinfunction "PGND_3") (pintype "passive"))
      (node (ref "U6") (pin "2") (pinfunction "GND_2") (pintype "passive"))
      (node (ref "U6") (pin "3") (pinfunction "GND_3") (pintype "passive"))
      (node (ref "U6") (pin "9") (pinfunction "PAD_9") (pintype "passive"))
      (node (ref "U7") (pin "11") (pinfunction "GND_11") (pintype "passive"))
      (node (ref "U7") (pin "12") (pinfunction "OUT4_12") (pintype "passive"))
      (node (ref "U7") (pin "13") (pinfunction "OUT3_13") (pintype "passive"))
      (node (ref "U7") (pin "17") (pinfunction "PGND_17") (pintype "passive"))
      (node (ref "U7") (pin "21") (pinfunction "PAD_21") (pintype "passive"))
      (node (ref "U7") (pin "9") (pinfunction "GND_9") (pintype "passive"))
      (node (ref "U8") (pin "11") (pinfunction "GND_11") (pintype "passive"))
      (node (ref "U8") (pin "12") (pinfunction "OUT4_12") (pintype "passive"))
      (node (ref "U8") (pin "13") (pinfunction "OUT3_13") (pintype "passive"))
      (node (ref "U8") (pin "17") (pinfunction "PGND_17") (pintype "passive"))
      (node (ref "U8") (pin "21") (pinfunction "PAD_21") (pintype "passive"))
      (node (ref "U8") (pin "9") (pinfunction "GND_9") (pintype "passive"))
      (node (ref "U9") (pin "2") (pinfunction "GND_2") (pintype "passive"))
    )
    (net (code "18") (name "LCD_BIAS_EN") (class "Default")
      (node (ref "U5") (pin "10") (pinfunction "ENN_10") (pintype "passive"))
      (node (ref "U5") (pin "11") (pinfunction "PSN_11") (pintype "passive"))
      (node (ref "U5") (pin "8") (pinfunction "ENP_8") (pintype "passive"))
      (node (ref "U5") (pin "9") (pinfunction "PSP_9") (pintype "passive"))
    )
    (net (code "19") (name "LCD_BL_EN") (class "Default")
      (node (ref "U7") (pin "4") (pinfunction "VDDIO/EN_4") (pintype "passive"))
      (node (ref "U7") (pin "6") (pinfunction "SYNC_6") (pintype "passive"))
      (node (ref "U8") (pin "4") (pinfunction "VDDIO/EN_4") (pintype "passive"))
      (node (ref "U8") (pin "6") (pinfunction "SYNC_6") (pintype "passive"))
    )
    (net (code "20") (name "LCD_BL_FAULT") (class "Default")
      (node (ref "U7") (pin "5") (pinfunction "FAULT_5") (pintype "passive"))
      (node (ref "U8") (pin "5") (pinfunction "FAULT_5") (pintype "passive"))
    )
    (net (code "21") (name "LCD_BL_K1_L") (class "Default")
      (node (ref "U7") (pin "14") (pinfunction "OUT2_14") (pintype "passive"))
    )
    (net (code "22") (name "LCD_BL_K1_R") (class "Default")
      (node (ref "U8") (pin "14") (pinfunction "OUT2_14") (pintype "passive"))
    )
    (net (code "23") (name "LCD_BL_K2_L") (class "Default")
      (node (ref "U7") (pin "15") (pinfunction "OUT1_15") (pintype "passive"))
    )
    (net (code "24") (name "LCD_BL_K2_R") (class "Default")
      (node (ref "U8") (pin "15") (pinfunction "OUT1_15") (pintype "passive"))
    )
    (net (code "25") (name "LCD_BL_PWM") (class "Default")
      (node (ref "U7") (pin "7") (pinfunction "PWM_7") (pintype "passive"))
      (node (ref "U8") (pin "7") (pinfunction "PWM_7") (pintype "passive"))
    )
    (net (code "26") (name "Net-(D2-PadA)") (class "Default")
      (node (ref "D2") (pin "A") (pinfunction "A_A") (pintype "passive"))
      (node (ref "L1") (pin "2") (pinfunction "2_2") (pintype "passive"))
      (node (ref "U5") (pin "1") (pinfunction "INP_1") (pintype "passive"))
      (node (ref "U5") (pin "24") (pinfunction "INP_24") (pintype "passive"))
    )
    (net (code "27") (name "Net-(D3-PadK)") (class "Default")
      (node (ref "D3") (pin "K") (pinfunction "K_K") (pintype "passive"))
      (node (ref "L4") (pin "1") (pinfunction "1_1") (pintype "passive"))
      (node (ref "U5") (pin "13") (pinfunction "OUTN_13") (pintype "passive"))
      (node (ref "U5") (pin "14") (pinfunction "OUTN_14") (pintype "passive"))
    )
    (net (code "28") (name "Net-(U4-FB)") (class "Default")
      (node (ref "R25") (pin "1") (pinfunction "1_1") (pintype "passive"))
      (node (ref "R27") (pin "2") (pinfunction "2_2") (pintype "passive"))
      (node (ref "U4") (pin "4") (pinfunction "FB_4") (pintype "passive"))
    )
    (net (code "29") (name "Net-(U4-SW)") (class "Default")
      (node (ref "L2") (pin "1") (pinfunction "1_1") (pintype "passive"))
      (node (ref "U4") (pin "7") (pinfunction "SW_7") (pintype "passive"))
    )
    (net (code "30") (name "Net-(U5-VIN)") (class "Default")
      (node (ref "C37") (pin "2") (pinfunction "2_2") (pintype "passive"))
      (node (ref "R31") (pin "2") (pinfunction "2_2") (pintype "passive"))
      (node (ref "U5") (pin "4") (pinfunction "VIN_4") (pintype "passive"))
    )
    (net (code "31") (name "Net-(U5-VREF)") (class "Default")
      (node (ref "C35") (pin "1") (pinfunction "1_1") (pintype "passive"))
      (node (ref "R29") (pin "1") (pinfunction "1_1") (pintype "passive"))
      (node (ref "U5") (pin "17") (pinfunction "VREF_17") (pintype "passive"))
    )
    (net (code "32") (name "Net-(U6-FB)") (class "Default")
      (node (ref "R33") (pin "1") (pinfunction "1_1") (pintype "passive"))
      (node (ref "R34") (pin "2") (pinfunction "2_2") (pintype "passive"))
      (node (ref "U6") (pin "4") (pinfunction "FB_4") (pintype "passive"))
    )
    (net (code "33") (name "Net-(U6-SW)") (class "Default")
      (node (ref "L3") (pin "1") (pinfunction "1_1") (pintype "passive"))
      (node (ref "U6") (pin "7") (pinfunction "SW_7") (pintype "passive"))
    )
    (net (code "34") (name "Net-(U7-FSET)") (class "Default")
      (node (ref "R39") (pin "2") (pinfunction "2_2") (pintype "passive"))
      (node (ref "U7") (pin "3") (pinfunction "FSET_3") (pintype "passive"))
    )
    (net (code "35") (name "Net-(U7-ISET)") (class "Default")
      (node (ref "R40") (pin "2") (pinfunction "2_2") (pintype "passive"))
      (node (ref "U7") (pin "10") (pinfunction "ISET_10") (pintype "passive"))
    )
    (net (code "36") (name "Net-(U7-LDO)") (class "Default")
      (node (ref "C55") (pin "1") (pinfunction "1_1") (pintype "passive"))
      (node (ref "U7") (pin "2") (pinfunction "LDO_2") (pintype "passive"))
    )
    (net (code "37") (name "Net-(U8-FSET)") (class "Default")
      (node (ref "R41") (pin "2") (pinfunction "2_2") (pintype "passive"))
      (node (ref "U8") (pin "3") (pinfunction "FSET_3") (pintype "passive"))
    )
    (net (code "38") (name "Net-(U8-ISET)") (class "Default")
      (node (ref "R42") (pin "2") (pinfunction "2_2") (pintype "passive"))
      (node (ref "U8") (pin "10") (pinfunction "ISET_10") (pintype "passive"))
    )
    (net (code "39") (name "Net-(U8-LDO)") (class "Default")
      (node (ref "C56") (pin "1") (pinfunction "1_1") (pintype "passive"))
      (node (ref "U8") (pin "2") (pinfunction "LDO_2") (pintype "passive"))
    )
    (net (code "40") (name "Net-(U9-OUT)") (class "Default")
      (node (ref "C6") (pin "1") (pinfunction "1_1") (pintype "passive"))
      (node (ref "R16") (pin "1") (pinfunction "1_1") (pintype "passive"))
      (node (ref "U9") (pin "5") (pinfunction "OUT_5") (pintype "passive"))
    )
    (net (code "41") (name "SW_L") (class "Default")
      (node (ref "D4") (pin "A") (pinfunction "A_A") (pintype "passive"))
      (node (ref "L5") (pin "2") (pinfunction "2_2") (pintype "passive"))
      (node (ref "U7") (pin "18") (pinfunction "SW_18") (pintype "passive"))
    )
    (net (code "42") (name "SW_R") (class "Default")
      (node (ref "D5") (pin "A") (pinfunction "A_A") (pintype "passive"))
      (node (ref "L6") (pin "2") (pinfunction "2_2") (pintype "passive"))
      (node (ref "U8") (pin "18") (pinfunction "SW_18") (pintype "passive"))
    )
    (net (code "43") (name "VNEG") (class "Default")
      (node (ref "C36") (pin "1") (pinfunction "1_1") (pintype "passive"))
      (node (ref "C38") (pin "2") (pinfunction "2_2") (pintype "passive"))
      (node (ref "C39") (pin "2") (pinfunction "2_2") (pintype "passive"))
      (node (ref "D3") (pin "A") (pinfunction "A_A") (pintype "passive"))
      (node (ref "R19") (pin "1") (pinfunction "1_1") (pintype "passive"))
      (node (ref "R30") (pin "1") (pinfunction "1_1") (pintype "passive"))
      (node (ref "U5") (pin "15") (pinfunction "VNEG_15") (pintype "passive"))
    )
    (net (code "44") (name "VPOS") (class "Default")
      (node (ref "C29") (pin "2") (pinfunction "2_2") (pintype "passive"))
      (node (ref "C30") (pin "2") (pinfunction "2_2") (pintype "passive"))
      (node (ref "C34") (pin "1") (pinfunction "1_1") (pintype "passive"))
      (node (ref "D2") (pin "K") (pinfunction "K_K") (pintype "passive"))
      (node (ref "R18") (pin "1") (pinfunction "1_1") (pintype "passive"))
      (node (ref "R26") (pin "1") (pinfunction "1_1") (pintype "passive"))
      (node (ref "U5") (pin "23") (pinfunction "VPOS_23") (pintype "passive"))
    )
    (net (code "45") (name "unconnected-(U4-PG-Pad6)") (class "Default")
      (node (ref "U4") (pin "6") (pinfunction "PG_6") (pintype "passive"))
    )
    (net (code "46") (name "unconnected-(U5-BSW-Pad7)") (class "Default")
      (node (ref "U5") (pin "7") (pinfunction "BSW_7") (pintype "passive"))
    )
    (net (code "47") (name "unconnected-(U5-NC-Pad12)") (class "Default")
      (node (ref "U5") (pin "12") (pinfunction "NC_12") (pintype "passive"))
    )
    (net (code "48") (name "unconnected-(U5-NC-Pad20)") (class "Default")
      (node (ref "U5") (pin "20") (pinfunction "NC_20") (pintype "passive"))
    )
    (net (code "49") (name "unconnected-(U6-PG-Pad6)") (class "Default")
      (node (ref "U6") (pin "6") (pinfunction "PG_6") (pintype "passive"))
    )
    (net (code "50") (name "unconnected-(U7-NC-Pad8)") (class "Default")
      (node (ref "U7") (pin "8") (pinfunction "NC_8") (pintype "passive"))
    )
    (net (code "51") (name "unconnected-(U7-NC-Pad19)") (class "Default")
      (node (ref "U7") (pin "19") (pinfunction "NC_19") (pintype "passive"))
    )
    (net (code "52") (name "unconnected-(U8-NC-Pad8)") (class "Default")
      (node (ref "U8") (pin "8") (pinfunction "NC_8") (pintype "passive"))
    )
    (net (code "53") (name "unconnected-(U8-NC-Pad19)") (class "Default")
      (node (ref "U8") (pin "19") (pinfunction "NC_19") (pintype "passive"))
    )
    (net (code "54") (name "unconnected-(U9-NC-Pad4)") (class "Default")
      (node (ref "U9") (pin "4") (pinfunction "NC_4") (pintype "passive"))
    )
  )
)
